# Cpcis_connectors_P4_P5_P6.net
KiCad netlist of a schematic drawn in Altium Designer
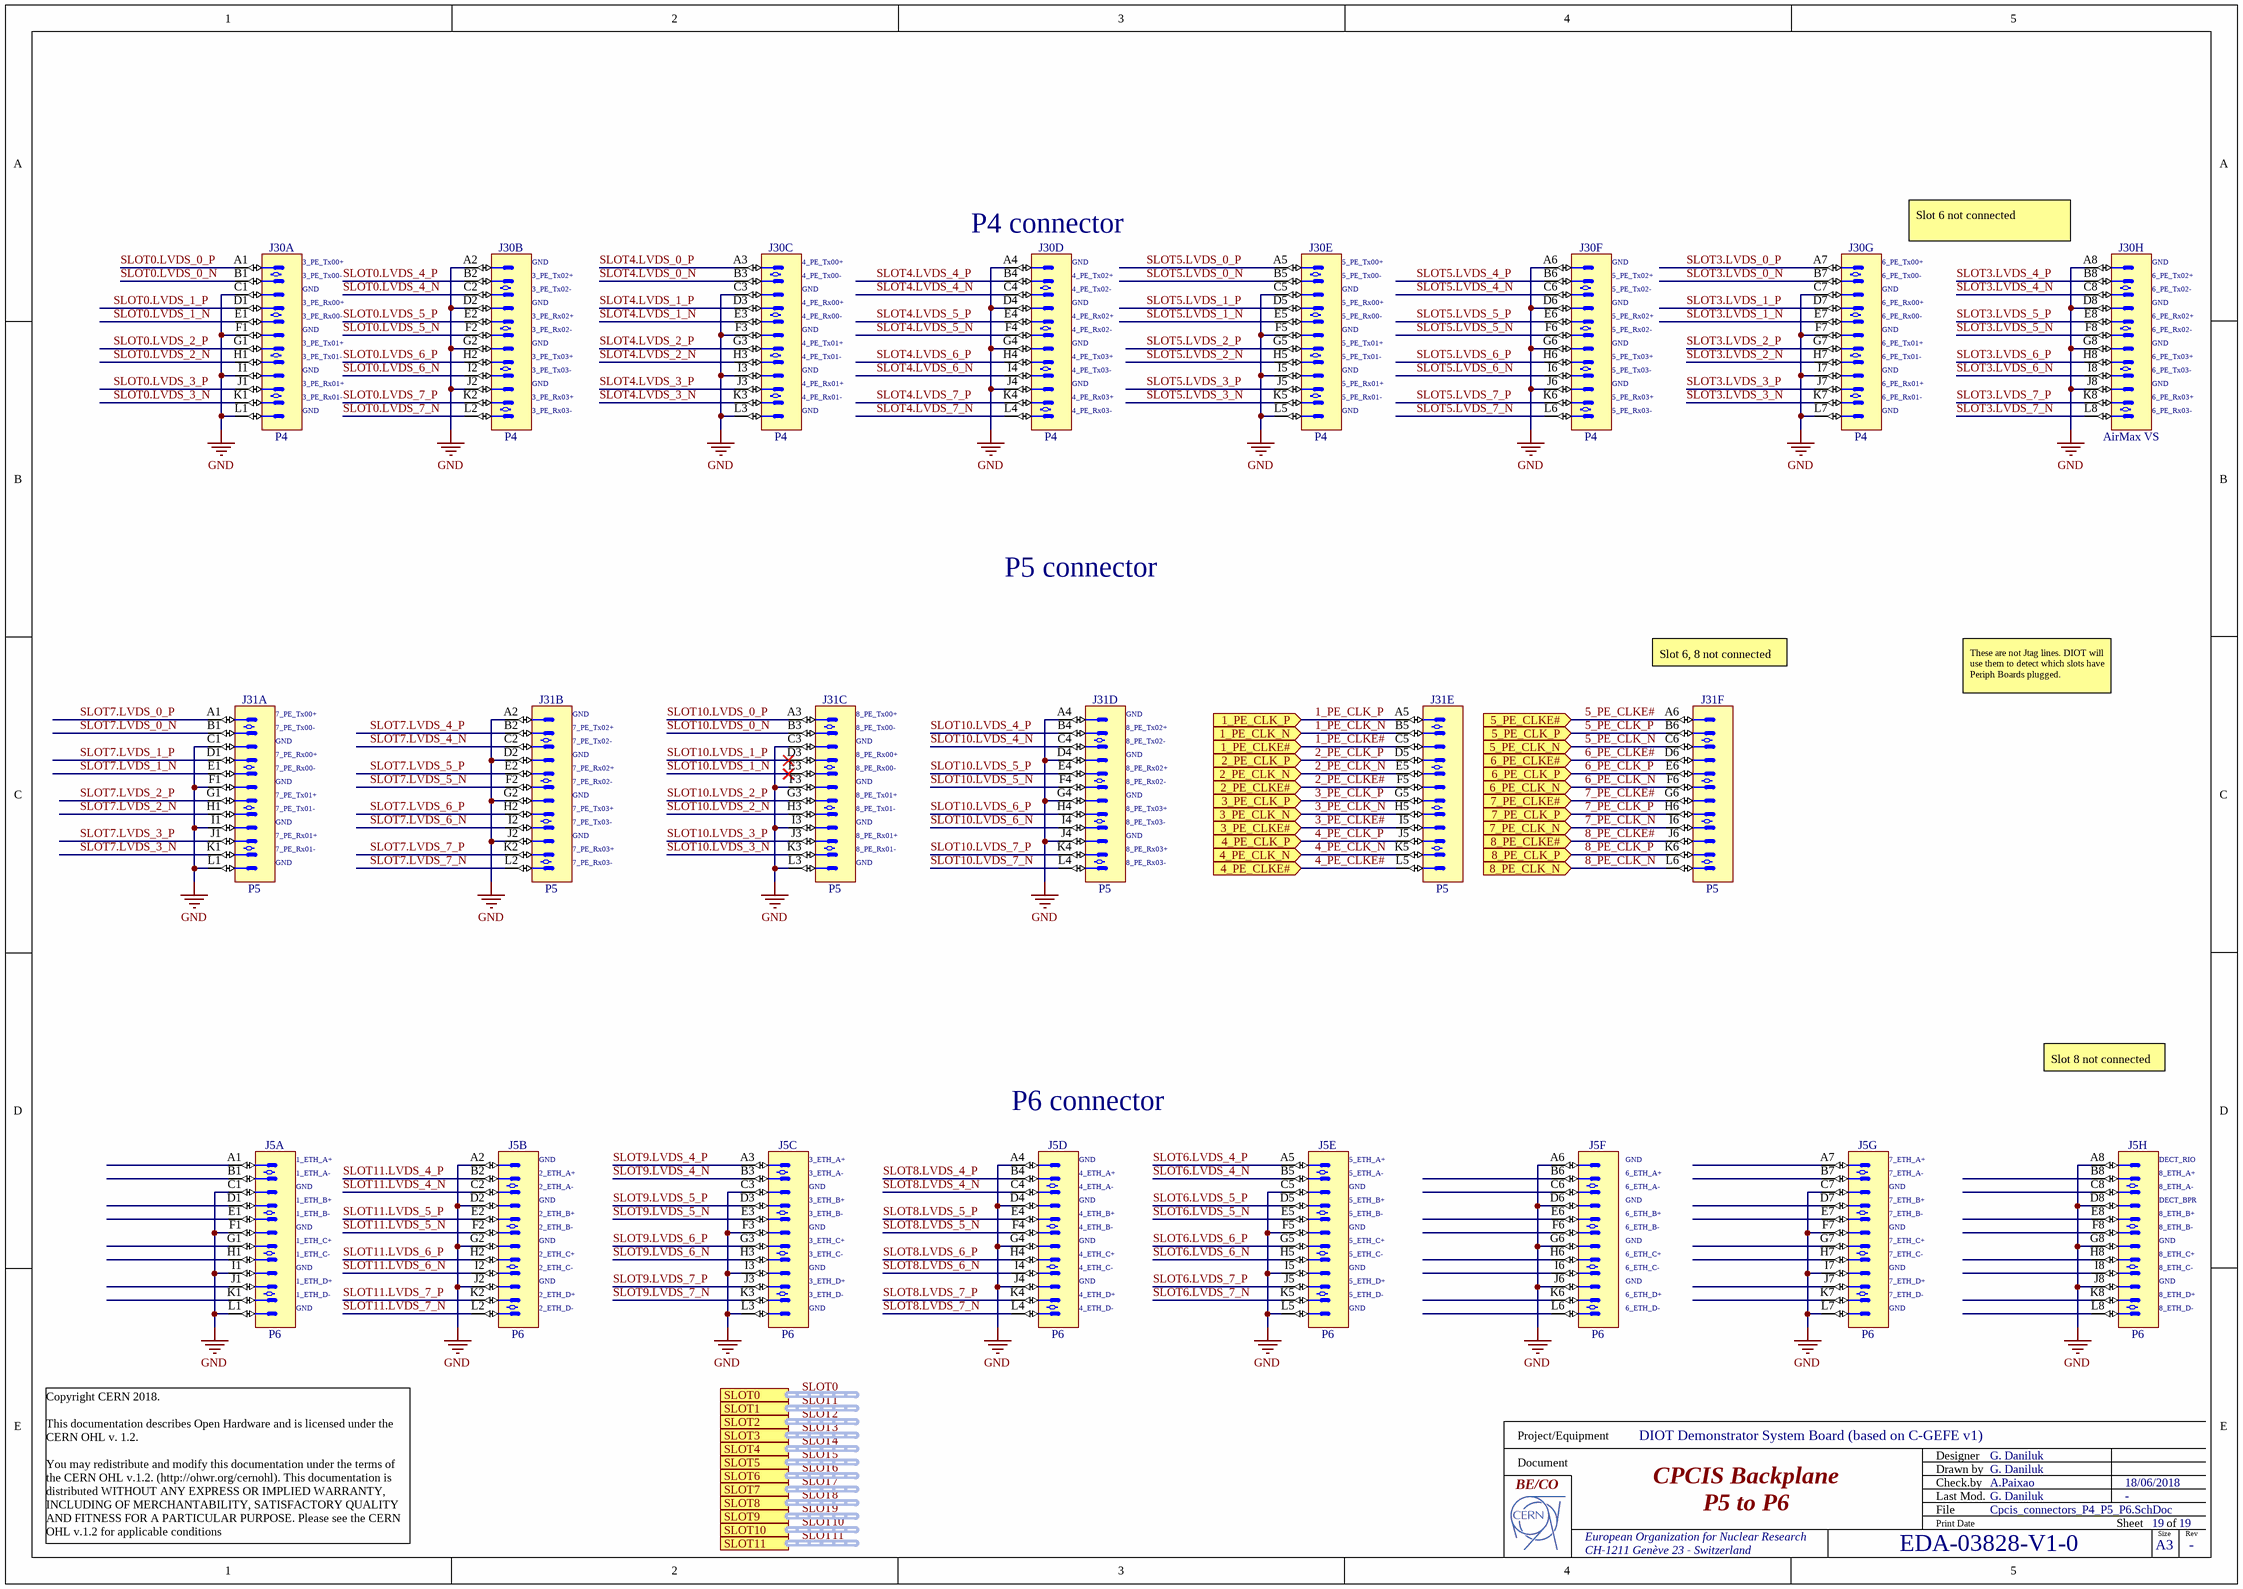
[diagram p0: Cpcis_connectors_P4_P5_P6.SchDoc]

(export (version "E")
  (design (tool "Eeschema 10.0.6"))
  (components
    (comp (ref "J5")
      (value "P6")
      (footprint "AMPHENOL_10052838-101LF")
      (description "96 Contacts Header, 8 Columns, 4 Pairs per Column")
      (fields
        (field (name "PART NUMBER") "AMPHENOL_10052838-101LF")
        (field (name "MANUFACTURER") "AMPHENOL")
        (field (name "AUTHOR") "CERN DEM MR")
      )
      (libsource (lib "Connectors") (part "AMPHENOL_10052838-101LF"))
    )
    (comp (ref "J30")
      (value "P4")
      (footprint "AMPHENOL_10052837-101LF")
      (description "96 Contacts Header, 8 Columns, 4 Pairs per Column")
      (fields
        (field (name "PART NUMBER") "AMPHENOL_10052837-101LF")
        (field (name "MANUFACTURER") "AMPHENOL")
        (field (name "AUTHOR") "CERN DEM MR")
      )
      (libsource (lib "Connectors") (part "AMPHENOL_10052837-101LF"))
    )
    (comp (ref "J31")
      (value "P5")
      (footprint "AMPHENOL_10052824-101LF")
      (description "72 Contacts Header, 6 Columns, 4 Pairs per Column")
      (fields
        (field (name "PART NUMBER") "AMPHENOL_10052824-101LF")
        (field (name "MANUFACTURER") "AMPHENOL")
        (field (name "AUTHOR") "CERN DEM JMW")
      )
      (libsource (lib "Connectors") (part "AMPHENOL_10052824-101LF"))
    )
  )
  (nets
    (net (code "13") (name "/1_PE_CLKE#") (class "Default")
      (node (ref "J31") (pin "C5") (pinfunction "C5_C5") (pintype "bidirectional"))
    )
    (net (code "14") (name "/1_PE_CLK_N") (class "Default")
      (node (ref "J31") (pin "B5") (pinfunction "B5_B5") (pintype "bidirectional"))
    )
    (net (code "15") (name "/1_PE_CLK_P") (class "Default")
      (node (ref "J31") (pin "A5") (pinfunction "A5_A5") (pintype "bidirectional"))
    )
    (net (code "16") (name "/2_PE_CLKE#") (class "Default")
      (node (ref "J31") (pin "F5") (pinfunction "F5_F5") (pintype "bidirectional"))
    )
    (net (code "17") (name "/2_PE_CLK_N") (class "Default")
      (node (ref "J31") (pin "E5") (pinfunction "E5_E5") (pintype "bidirectional"))
    )
    (net (code "18") (name "/2_PE_CLK_P") (class "Default")
      (node (ref "J31") (pin "D5") (pinfunction "D5_D5") (pintype "bidirectional"))
    )
    (net (code "19") (name "/3_PE_CLKE#") (class "Default")
      (node (ref "J31") (pin "I5") (pinfunction "I5_I5") (pintype "bidirectional"))
    )
    (net (code "20") (name "/3_PE_CLK_N") (class "Default")
      (node (ref "J31") (pin "H5") (pinfunction "H5_H5") (pintype "bidirectional"))
    )
    (net (code "21") (name "/3_PE_CLK_P") (class "Default")
      (node (ref "J31") (pin "G5") (pinfunction "G5_G5") (pintype "bidirectional"))
    )
    (net (code "22") (name "/4_PE_CLKE#") (class "Default")
      (node (ref "J31") (pin "L5") (pinfunction "L5_L5") (pintype "bidirectional"))
    )
    (net (code "23") (name "/4_PE_CLK_N") (class "Default")
      (node (ref "J31") (pin "K5") (pinfunction "K5_K5") (pintype "bidirectional"))
    )
    (net (code "24") (name "/4_PE_CLK_P") (class "Default")
      (node (ref "J31") (pin "J5") (pinfunction "J5_J5") (pintype "bidirectional"))
    )
    (net (code "25") (name "/5_PE_CLKE#") (class "Default")
      (node (ref "J31") (pin "A6") (pinfunction "A6_A6") (pintype "bidirectional"))
    )
    (net (code "26") (name "/5_PE_CLK_N") (class "Default")
      (node (ref "J31") (pin "C6") (pinfunction "C6_C6") (pintype "bidirectional"))
    )
    (net (code "27") (name "/5_PE_CLK_P") (class "Default")
      (node (ref "J31") (pin "B6") (pinfunction "B6_B6") (pintype "bidirectional"))
    )
    (net (code "28") (name "/6_PE_CLKE#") (class "Default")
      (node (ref "J31") (pin "D6") (pinfunction "D6_D6") (pintype "bidirectional"))
    )
    (net (code "29") (name "/6_PE_CLK_N") (class "Default")
      (node (ref "J31") (pin "F6") (pinfunction "F6_F6") (pintype "bidirectional"))
    )
    (net (code "30") (name "/6_PE_CLK_P") (class "Default")
      (node (ref "J31") (pin "E6") (pinfunction "E6_E6") (pintype "bidirectional"))
    )
    (net (code "31") (name "/7_PE_CLKE#") (class "Default")
      (node (ref "J31") (pin "G6") (pinfunction "G6_G6") (pintype "bidirectional"))
    )
    (net (code "32") (name "/7_PE_CLK_N") (class "Default")
      (node (ref "J31") (pin "I6") (pinfunction "I6_I6") (pintype "bidirectional"))
    )
    (net (code "33") (name "/7_PE_CLK_P") (class "Default")
      (node (ref "J31") (pin "H6") (pinfunction "H6_H6") (pintype "bidirectional"))
    )
    (net (code "34") (name "/8_PE_CLKE#") (class "Default")
      (node (ref "J31") (pin "J6") (pinfunction "J6_J6") (pintype "bidirectional"))
    )
    (net (code "35") (name "/8_PE_CLK_N") (class "Default")
      (node (ref "J31") (pin "L6") (pinfunction "L6_L6") (pintype "bidirectional"))
    )
    (net (code "36") (name "/8_PE_CLK_P") (class "Default")
      (node (ref "J31") (pin "K6") (pinfunction "K6_K6") (pintype "bidirectional"))
    )
    (net (code "37") (name "/SLOT0.LVDS_0_N") (class "Default")
      (node (ref "J30") (pin "B1") (pinfunction "B1_B1") (pintype "bidirectional"))
    )
    (net (code "38") (name "/SLOT0.LVDS_0_P") (class "Default")
      (node (ref "J30") (pin "A1") (pinfunction "A1_A1") (pintype "bidirectional"))
    )
    (net (code "39") (name "/SLOT0.LVDS_1_N") (class "Default")
      (node (ref "J30") (pin "E1") (pinfunction "E1_E1") (pintype "bidirectional"))
    )
    (net (code "40") (name "/SLOT0.LVDS_1_P") (class "Default")
      (node (ref "J30") (pin "D1") (pinfunction "D1_D1") (pintype "bidirectional"))
    )
    (net (code "41") (name "/SLOT0.LVDS_2_N") (class "Default")
      (node (ref "J30") (pin "H1") (pinfunction "H1_H1") (pintype "bidirectional"))
    )
    (net (code "42") (name "/SLOT0.LVDS_2_P") (class "Default")
      (node (ref "J30") (pin "G1") (pinfunction "G1_G1") (pintype "bidirectional"))
    )
    (net (code "43") (name "/SLOT0.LVDS_3_N") (class "Default")
      (node (ref "J30") (pin "K1") (pinfunction "K1_K1") (pintype "bidirectional"))
    )
    (net (code "44") (name "/SLOT0.LVDS_3_P") (class "Default")
      (node (ref "J30") (pin "J1") (pinfunction "J1_J1") (pintype "bidirectional"))
    )
    (net (code "45") (name "/SLOT0.LVDS_4_N") (class "Default")
      (node (ref "J30") (pin "C2") (pinfunction "C2_C2") (pintype "bidirectional"))
    )
    (net (code "46") (name "/SLOT0.LVDS_4_P") (class "Default")
      (node (ref "J30") (pin "B2") (pinfunction "B2_B2") (pintype "bidirectional"))
    )
    (net (code "47") (name "/SLOT0.LVDS_5_N") (class "Default")
      (node (ref "J30") (pin "F2") (pinfunction "F2_F2") (pintype "bidirectional"))
    )
    (net (code "48") (name "/SLOT0.LVDS_5_P") (class "Default")
      (node (ref "J30") (pin "E2") (pinfunction "E2_E2") (pintype "bidirectional"))
    )
    (net (code "49") (name "/SLOT0.LVDS_6_N") (class "Default")
      (node (ref "J30") (pin "I2") (pinfunction "I2_I2") (pintype "bidirectional"))
    )
    (net (code "50") (name "/SLOT0.LVDS_6_P") (class "Default")
      (node (ref "J30") (pin "H2") (pinfunction "H2_H2") (pintype "bidirectional"))
    )
    (net (code "51") (name "/SLOT0.LVDS_7_N") (class "Default")
      (node (ref "J30") (pin "L2") (pinfunction "L2_L2") (pintype "bidirectional"))
    )
    (net (code "52") (name "/SLOT0.LVDS_7_P") (class "Default")
      (node (ref "J30") (pin "K2") (pinfunction "K2_K2") (pintype "bidirectional"))
    )
    (net (code "53") (name "/SLOT3.LVDS_0_N") (class "Default")
      (node (ref "J30") (pin "B7") (pinfunction "B7_B7") (pintype "bidirectional"))
    )
    (net (code "54") (name "/SLOT3.LVDS_0_P") (class "Default")
      (node (ref "J30") (pin "A7") (pinfunction "A7_A7") (pintype "bidirectional"))
    )
    (net (code "55") (name "/SLOT3.LVDS_1_N") (class "Default")
      (node (ref "J30") (pin "E7") (pinfunction "E7_E7") (pintype "bidirectional"))
    )
    (net (code "56") (name "/SLOT3.LVDS_1_P") (class "Default")
      (node (ref "J30") (pin "D7") (pinfunction "D7_D7") (pintype "bidirectional"))
    )
    (net (code "57") (name "/SLOT3.LVDS_2_N") (class "Default")
      (node (ref "J30") (pin "H7") (pinfunction "H7_H7") (pintype "bidirectional"))
    )
    (net (code "58") (name "/SLOT3.LVDS_2_P") (class "Default")
      (node (ref "J30") (pin "G7") (pinfunction "G7_G7") (pintype "bidirectional"))
    )
    (net (code "59") (name "/SLOT3.LVDS_3_N") (class "Default")
      (node (ref "J30") (pin "K7") (pinfunction "K7_K7") (pintype "bidirectional"))
    )
    (net (code "60") (name "/SLOT3.LVDS_3_P") (class "Default")
      (node (ref "J30") (pin "J7") (pinfunction "J7_J7") (pintype "bidirectional"))
    )
    (net (code "61") (name "/SLOT3.LVDS_4_N") (class "Default")
      (node (ref "J30") (pin "C8") (pinfunction "C8_C8") (pintype "bidirectional"))
    )
    (net (code "62") (name "/SLOT3.LVDS_4_P") (class "Default")
      (node (ref "J30") (pin "B8") (pinfunction "B8_B8") (pintype "bidirectional"))
    )
    (net (code "63") (name "/SLOT3.LVDS_5_N") (class "Default")
      (node (ref "J30") (pin "F8") (pinfunction "F8_F8") (pintype "bidirectional"))
    )
    (net (code "64") (name "/SLOT3.LVDS_5_P") (class "Default")
      (node (ref "J30") (pin "E8") (pinfunction "E8_E8") (pintype "bidirectional"))
    )
    (net (code "65") (name "/SLOT3.LVDS_6_N") (class "Default")
      (node (ref "J30") (pin "I8") (pinfunction "I8_I8") (pintype "bidirectional"))
    )
    (net (code "66") (name "/SLOT3.LVDS_6_P") (class "Default")
      (node (ref "J30") (pin "H8") (pinfunction "H8_H8") (pintype "bidirectional"))
    )
    (net (code "67") (name "/SLOT3.LVDS_7_N") (class "Default")
      (node (ref "J30") (pin "L8") (pinfunction "L8_L8") (pintype "bidirectional"))
    )
    (net (code "68") (name "/SLOT3.LVDS_7_P") (class "Default")
      (node (ref "J30") (pin "K8") (pinfunction "K8_K8") (pintype "bidirectional"))
    )
    (net (code "69") (name "/SLOT4.LVDS_0_N") (class "Default")
      (node (ref "J30") (pin "B3") (pinfunction "B3_B3") (pintype "bidirectional"))
    )
    (net (code "70") (name "/SLOT4.LVDS_0_P") (class "Default")
      (node (ref "J30") (pin "A3") (pinfunction "A3_A3") (pintype "bidirectional"))
    )
    (net (code "71") (name "/SLOT4.LVDS_1_N") (class "Default")
      (node (ref "J30") (pin "E3") (pinfunction "E3_E3") (pintype "bidirectional"))
    )
    (net (code "72") (name "/SLOT4.LVDS_1_P") (class "Default")
      (node (ref "J30") (pin "D3") (pinfunction "D3_D3") (pintype "bidirectional"))
    )
    (net (code "73") (name "/SLOT4.LVDS_2_N") (class "Default")
      (node (ref "J30") (pin "H3") (pinfunction "H3_H3") (pintype "bidirectional"))
    )
    (net (code "74") (name "/SLOT4.LVDS_2_P") (class "Default")
      (node (ref "J30") (pin "G3") (pinfunction "G3_G3") (pintype "bidirectional"))
    )
    (net (code "75") (name "/SLOT4.LVDS_3_N") (class "Default")
      (node (ref "J30") (pin "K3") (pinfunction "K3_K3") (pintype "bidirectional"))
    )
    (net (code "76") (name "/SLOT4.LVDS_3_P") (class "Default")
      (node (ref "J30") (pin "J3") (pinfunction "J3_J3") (pintype "bidirectional"))
    )
    (net (code "77") (name "/SLOT4.LVDS_4_N") (class "Default")
      (node (ref "J30") (pin "C4") (pinfunction "C4_C4") (pintype "bidirectional"))
    )
    (net (code "78") (name "/SLOT4.LVDS_4_P") (class "Default")
      (node (ref "J30") (pin "B4") (pinfunction "B4_B4") (pintype "bidirectional"))
    )
    (net (code "79") (name "/SLOT4.LVDS_5_N") (class "Default")
      (node (ref "J30") (pin "F4") (pinfunction "F4_F4") (pintype "bidirectional"))
    )
    (net (code "80") (name "/SLOT4.LVDS_5_P") (class "Default")
      (node (ref "J30") (pin "E4") (pinfunction "E4_E4") (pintype "bidirectional"))
    )
    (net (code "81") (name "/SLOT4.LVDS_6_N") (class "Default")
      (node (ref "J30") (pin "I4") (pinfunction "I4_I4") (pintype "bidirectional"))
    )
    (net (code "82") (name "/SLOT4.LVDS_6_P") (class "Default")
      (node (ref "J30") (pin "H4") (pinfunction "H4_H4") (pintype "bidirectional"))
    )
    (net (code "83") (name "/SLOT4.LVDS_7_N") (class "Default")
      (node (ref "J30") (pin "L4") (pinfunction "L4_L4") (pintype "bidirectional"))
    )
    (net (code "84") (name "/SLOT4.LVDS_7_P") (class "Default")
      (node (ref "J30") (pin "K4") (pinfunction "K4_K4") (pintype "bidirectional"))
    )
    (net (code "85") (name "/SLOT5.LVDS_0_N") (class "Default")
      (node (ref "J30") (pin "B5") (pinfunction "B5_B5") (pintype "bidirectional"))
    )
    (net (code "86") (name "/SLOT5.LVDS_0_P") (class "Default")
      (node (ref "J30") (pin "A5") (pinfunction "A5_A5") (pintype "bidirectional"))
    )
    (net (code "87") (name "/SLOT5.LVDS_1_N") (class "Default")
      (node (ref "J30") (pin "E5") (pinfunction "E5_E5") (pintype "bidirectional"))
    )
    (net (code "88") (name "/SLOT5.LVDS_1_P") (class "Default")
      (node (ref "J30") (pin "D5") (pinfunction "D5_D5") (pintype "bidirectional"))
    )
    (net (code "89") (name "/SLOT5.LVDS_2_N") (class "Default")
      (node (ref "J30") (pin "H5") (pinfunction "H5_H5") (pintype "bidirectional"))
    )
    (net (code "90") (name "/SLOT5.LVDS_2_P") (class "Default")
      (node (ref "J30") (pin "G5") (pinfunction "G5_G5") (pintype "bidirectional"))
    )
    (net (code "91") (name "/SLOT5.LVDS_3_N") (class "Default")
      (node (ref "J30") (pin "K5") (pinfunction "K5_K5") (pintype "bidirectional"))
    )
    (net (code "92") (name "/SLOT5.LVDS_3_P") (class "Default")
      (node (ref "J30") (pin "J5") (pinfunction "J5_J5") (pintype "bidirectional"))
    )
    (net (code "93") (name "/SLOT5.LVDS_4_N") (class "Default")
      (node (ref "J30") (pin "C6") (pinfunction "C6_C6") (pintype "bidirectional"))
    )
    (net (code "94") (name "/SLOT5.LVDS_4_P") (class "Default")
      (node (ref "J30") (pin "B6") (pinfunction "B6_B6") (pintype "bidirectional"))
    )
    (net (code "95") (name "/SLOT5.LVDS_5_N") (class "Default")
      (node (ref "J30") (pin "F6") (pinfunction "F6_F6") (pintype "bidirectional"))
    )
    (net (code "96") (name "/SLOT5.LVDS_5_P") (class "Default")
      (node (ref "J30") (pin "E6") (pinfunction "E6_E6") (pintype "bidirectional"))
    )
    (net (code "97") (name "/SLOT5.LVDS_6_N") (class "Default")
      (node (ref "J30") (pin "I6") (pinfunction "I6_I6") (pintype "bidirectional"))
    )
    (net (code "98") (name "/SLOT5.LVDS_6_P") (class "Default")
      (node (ref "J30") (pin "H6") (pinfunction "H6_H6") (pintype "bidirectional"))
    )
    (net (code "99") (name "/SLOT5.LVDS_7_N") (class "Default")
      (node (ref "J30") (pin "L6") (pinfunction "L6_L6") (pintype "bidirectional"))
    )
    (net (code "100") (name "/SLOT5.LVDS_7_P") (class "Default")
      (node (ref "J30") (pin "K6") (pinfunction "K6_K6") (pintype "bidirectional"))
    )
    (net (code "101") (name "/SLOT6.LVDS_4_N") (class "Default")
      (node (ref "J5") (pin "B5") (pinfunction "B5_B5") (pintype "bidirectional"))
    )
    (net (code "102") (name "/SLOT6.LVDS_4_P") (class "Default")
      (node (ref "J5") (pin "A5") (pinfunction "A5_A5") (pintype "bidirectional"))
    )
    (net (code "103") (name "/SLOT6.LVDS_5_N") (class "Default")
      (node (ref "J5") (pin "E5") (pinfunction "E5_E5") (pintype "bidirectional"))
    )
    (net (code "104") (name "/SLOT6.LVDS_5_P") (class "Default")
      (node (ref "J5") (pin "D5") (pinfunction "D5_D5") (pintype "bidirectional"))
    )
    (net (code "105") (name "/SLOT6.LVDS_6_N") (class "Default")
      (node (ref "J5") (pin "H5") (pinfunction "H5_H5") (pintype "bidirectional"))
    )
    (net (code "106") (name "/SLOT6.LVDS_6_P") (class "Default")
      (node (ref "J5") (pin "G5") (pinfunction "G5_G5") (pintype "bidirectional"))
    )
    (net (code "107") (name "/SLOT6.LVDS_7_N") (class "Default")
      (node (ref "J5") (pin "K5") (pinfunction "K5_K5") (pintype "bidirectional"))
    )
    (net (code "108") (name "/SLOT6.LVDS_7_P") (class "Default")
      (node (ref "J5") (pin "J5") (pinfunction "J5_J5") (pintype "bidirectional"))
    )
    (net (code "109") (name "/SLOT7.LVDS_0_N") (class "Default")
      (node (ref "J31") (pin "B1") (pinfunction "B1_B1") (pintype "bidirectional"))
    )
    (net (code "110") (name "/SLOT7.LVDS_0_P") (class "Default")
      (node (ref "J31") (pin "A1") (pinfunction "A1_A1") (pintype "bidirectional"))
    )
    (net (code "111") (name "/SLOT7.LVDS_1_N") (class "Default")
      (node (ref "J31") (pin "E1") (pinfunction "E1_E1") (pintype "bidirectional"))
    )
    (net (code "112") (name "/SLOT7.LVDS_1_P") (class "Default")
      (node (ref "J31") (pin "D1") (pinfunction "D1_D1") (pintype "bidirectional"))
    )
    (net (code "113") (name "/SLOT7.LVDS_2_N") (class "Default")
      (node (ref "J31") (pin "H1") (pinfunction "H1_H1") (pintype "bidirectional"))
    )
    (net (code "114") (name "/SLOT7.LVDS_2_P") (class "Default")
      (node (ref "J31") (pin "G1") (pinfunction "G1_G1") (pintype "bidirectional"))
    )
    (net (code "115") (name "/SLOT7.LVDS_3_N") (class "Default")
      (node (ref "J31") (pin "K1") (pinfunction "K1_K1") (pintype "bidirectional"))
    )
    (net (code "116") (name "/SLOT7.LVDS_3_P") (class "Default")
      (node (ref "J31") (pin "J1") (pinfunction "J1_J1") (pintype "bidirectional"))
    )
    (net (code "117") (name "/SLOT7.LVDS_4_N") (class "Default")
      (node (ref "J31") (pin "C2") (pinfunction "C2_C2") (pintype "bidirectional"))
    )
    (net (code "118") (name "/SLOT7.LVDS_4_P") (class "Default")
      (node (ref "J31") (pin "B2") (pinfunction "B2_B2") (pintype "bidirectional"))
    )
    (net (code "119") (name "/SLOT7.LVDS_5_N") (class "Default")
      (node (ref "J31") (pin "F2") (pinfunction "F2_F2") (pintype "bidirectional"))
    )
    (net (code "120") (name "/SLOT7.LVDS_5_P") (class "Default")
      (node (ref "J31") (pin "E2") (pinfunction "E2_E2") (pintype "bidirectional"))
    )
    (net (code "121") (name "/SLOT7.LVDS_6_N") (class "Default")
      (node (ref "J31") (pin "I2") (pinfunction "I2_I2") (pintype "bidirectional"))
    )
    (net (code "122") (name "/SLOT7.LVDS_6_P") (class "Default")
      (node (ref "J31") (pin "H2") (pinfunction "H2_H2") (pintype "bidirectional"))
    )
    (net (code "123") (name "/SLOT7.LVDS_7_N") (class "Default")
      (node (ref "J31") (pin "L2") (pinfunction "L2_L2") (pintype "bidirectional"))
    )
    (net (code "124") (name "/SLOT7.LVDS_7_P") (class "Default")
      (node (ref "J31") (pin "K2") (pinfunction "K2_K2") (pintype "bidirectional"))
    )
    (net (code "125") (name "/SLOT8.LVDS_4_N") (class "Default")
      (node (ref "J5") (pin "C4") (pinfunction "C4_C4") (pintype "bidirectional"))
    )
    (net (code "126") (name "/SLOT8.LVDS_4_P") (class "Default")
      (node (ref "J5") (pin "B4") (pinfunction "B4_B4") (pintype "bidirectional"))
    )
    (net (code "127") (name "/SLOT8.LVDS_5_N") (class "Default")
      (node (ref "J5") (pin "F4") (pinfunction "F4_F4") (pintype "bidirectional"))
    )
    (net (code "128") (name "/SLOT8.LVDS_5_P") (class "Default")
      (node (ref "J5") (pin "E4") (pinfunction "E4_E4") (pintype "bidirectional"))
    )
    (net (code "129") (name "/SLOT8.LVDS_6_N") (class "Default")
      (node (ref "J5") (pin "I4") (pinfunction "I4_I4") (pintype "bidirectional"))
    )
    (net (code "130") (name "/SLOT8.LVDS_6_P") (class "Default")
      (node (ref "J5") (pin "H4") (pinfunction "H4_H4") (pintype "bidirectional"))
    )
    (net (code "131") (name "/SLOT8.LVDS_7_N") (class "Default")
      (node (ref "J5") (pin "L4") (pinfunction "L4_L4") (pintype "bidirectional"))
    )
    (net (code "132") (name "/SLOT8.LVDS_7_P") (class "Default")
      (node (ref "J5") (pin "K4") (pinfunction "K4_K4") (pintype "bidirectional"))
    )
    (net (code "133") (name "/SLOT9.LVDS_4_N") (class "Default")
      (node (ref "J5") (pin "B3") (pinfunction "B3_B3") (pintype "bidirectional"))
    )
    (net (code "134") (name "/SLOT9.LVDS_4_P") (class "Default")
      (node (ref "J5") (pin "A3") (pinfunction "A3_A3") (pintype "bidirectional"))
    )
    (net (code "135") (name "/SLOT9.LVDS_5_N") (class "Default")
      (node (ref "J5") (pin "E3") (pinfunction "E3_E3") (pintype "bidirectional"))
    )
    (net (code "136") (name "/SLOT9.LVDS_5_P") (class "Default")
      (node (ref "J5") (pin "D3") (pinfunction "D3_D3") (pintype "bidirectional"))
    )
    (net (code "137") (name "/SLOT9.LVDS_6_N") (class "Default")
      (node (ref "J5") (pin "H3") (pinfunction "H3_H3") (pintype "bidirectional"))
    )
    (net (code "138") (name "/SLOT9.LVDS_6_P") (class "Default")
      (node (ref "J5") (pin "G3") (pinfunction "G3_G3") (pintype "bidirectional"))
    )
    (net (code "139") (name "/SLOT9.LVDS_7_N") (class "Default")
      (node (ref "J5") (pin "K3") (pinfunction "K3_K3") (pintype "bidirectional"))
    )
    (net (code "140") (name "/SLOT9.LVDS_7_P") (class "Default")
      (node (ref "J5") (pin "J3") (pinfunction "J3_J3") (pintype "bidirectional"))
    )
    (net (code "141") (name "/SLOT10.LVDS_0_N") (class "Default")
      (node (ref "J31") (pin "B3") (pinfunction "B3_B3") (pintype "bidirectional"))
    )
    (net (code "142") (name "/SLOT10.LVDS_0_P") (class "Default")
      (node (ref "J31") (pin "A3") (pinfunction "A3_A3") (pintype "bidirectional"))
    )
    (net (code "143") (name "/SLOT10.LVDS_1_N") (class "Default")
      (node (ref "J31") (pin "E3") (pinfunction "E3_E3") (pintype "bidirectional+no_connect"))
    )
    (net (code "144") (name "/SLOT10.LVDS_1_P") (class "Default")
      (node (ref "J31") (pin "D3") (pinfunction "D3_D3") (pintype "bidirectional+no_connect"))
    )
    (net (code "145") (name "/SLOT10.LVDS_2_N") (class "Default")
      (node (ref "J31") (pin "H3") (pinfunction "H3_H3") (pintype "bidirectional"))
    )
    (net (code "146") (name "/SLOT10.LVDS_2_P") (class "Default")
      (node (ref "J31") (pin "G3") (pinfunction "G3_G3") (pintype "bidirectional"))
    )
    (net (code "147") (name "/SLOT10.LVDS_3_N") (class "Default")
      (node (ref "J31") (pin "K3") (pinfunction "K3_K3") (pintype "bidirectional"))
    )
    (net (code "148") (name "/SLOT10.LVDS_3_P") (class "Default")
      (node (ref "J31") (pin "J3") (pinfunction "J3_J3") (pintype "bidirectional"))
    )
    (net (code "149") (name "/SLOT10.LVDS_4_N") (class "Default")
      (node (ref "J31") (pin "C4") (pinfunction "C4_C4") (pintype "bidirectional"))
    )
    (net (code "150") (name "/SLOT10.LVDS_4_P") (class "Default")
      (node (ref "J31") (pin "B4") (pinfunction "B4_B4") (pintype "bidirectional"))
    )
    (net (code "151") (name "/SLOT10.LVDS_5_N") (class "Default")
      (node (ref "J31") (pin "F4") (pinfunction "F4_F4") (pintype "bidirectional"))
    )
    (net (code "152") (name "/SLOT10.LVDS_5_P") (class "Default")
      (node (ref "J31") (pin "E4") (pinfunction "E4_E4") (pintype "bidirectional"))
    )
    (net (code "153") (name "/SLOT10.LVDS_6_N") (class "Default")
      (node (ref "J31") (pin "I4") (pinfunction "I4_I4") (pintype "bidirectional"))
    )
    (net (code "154") (name "/SLOT10.LVDS_6_P") (class "Default")
      (node (ref "J31") (pin "H4") (pinfunction "H4_H4") (pintype "bidirectional"))
    )
    (net (code "155") (name "/SLOT10.LVDS_7_N") (class "Default")
      (node (ref "J31") (pin "L4") (pinfunction "L4_L4") (pintype "bidirectional"))
    )
    (net (code "156") (name "/SLOT10.LVDS_7_P") (class "Default")
      (node (ref "J31") (pin "K4") (pinfunction "K4_K4") (pintype "bidirectional"))
    )
    (net (code "157") (name "/SLOT11.LVDS_4_N") (class "Default")
      (node (ref "J5") (pin "C2") (pinfunction "C2_C2") (pintype "bidirectional"))
    )
    (net (code "158") (name "/SLOT11.LVDS_4_P") (class "Default")
      (node (ref "J5") (pin "B2") (pinfunction "B2_B2") (pintype "bidirectional"))
    )
    (net (code "159") (name "/SLOT11.LVDS_5_N") (class "Default")
      (node (ref "J5") (pin "F2") (pinfunction "F2_F2") (pintype "bidirectional"))
    )
    (net (code "160") (name "/SLOT11.LVDS_5_P") (class "Default")
      (node (ref "J5") (pin "E2") (pinfunction "E2_E2") (pintype "bidirectional"))
    )
    (net (code "161") (name "/SLOT11.LVDS_6_N") (class "Default")
      (node (ref "J5") (pin "I2") (pinfunction "I2_I2") (pintype "bidirectional"))
    )
    (net (code "162") (name "/SLOT11.LVDS_6_P") (class "Default")
      (node (ref "J5") (pin "H2") (pinfunction "H2_H2") (pintype "bidirectional"))
    )
    (net (code "163") (name "/SLOT11.LVDS_7_N") (class "Default")
      (node (ref "J5") (pin "L2") (pinfunction "L2_L2") (pintype "bidirectional"))
    )
    (net (code "164") (name "/SLOT11.LVDS_7_P") (class "Default")
      (node (ref "J5") (pin "K2") (pinfunction "K2_K2") (pintype "bidirectional"))
    )
    (net (code "177") (name "GND") (class "Default")
      (node (ref "J30") (pin "A2") (pinfunction "A2_A2") (pintype "bidirectional"))
      (node (ref "J30") (pin "A4") (pinfunction "A4_A4") (pintype "bidirectional"))
      (node (ref "J30") (pin "A6") (pinfunction "A6_A6") (pintype "bidirectional"))
      (node (ref "J30") (pin "A8") (pinfunction "A8_A8") (pintype "bidirectional"))
      (node (ref "J30") (pin "C1") (pinfunction "C1_C1") (pintype "bidirectional"))
      (node (ref "J30") (pin "C3") (pinfunction "C3_C3") (pintype "bidirectional"))
      (node (ref "J30") (pin "C5") (pinfunction "C5_C5") (pintype "bidirectional"))
      (node (ref "J30") (pin "C7") (pinfunction "C7_C7") (pintype "bidirectional"))
      (node (ref "J30") (pin "D2") (pinfunction "D2_D2") (pintype "bidirectional"))
      (node (ref "J30") (pin "D4") (pinfunction "D4_D4") (pintype "bidirectional"))
      (node (ref "J30") (pin "D6") (pinfunction "D6_D6") (pintype "bidirectional"))
      (node (ref "J30") (pin "D8") (pinfunction "D8_D8") (pintype "bidirectional"))
      (node (ref "J30") (pin "F1") (pinfunction "F1_F1") (pintype "bidirectional"))
      (node (ref "J30") (pin "F3") (pinfunction "F3_F3") (pintype "bidirectional"))
      (node (ref "J30") (pin "F5") (pinfunction "F5_F5") (pintype "bidirectional"))
      (node (ref "J30") (pin "F7") (pinfunction "F7_F7") (pintype "bidirectional"))
      (node (ref "J30") (pin "G2") (pinfunction "G2_G2") (pintype "bidirectional"))
      (node (ref "J30") (pin "G4") (pinfunction "G4_G4") (pintype "bidirectional"))
      (node (ref "J30") (pin "G6") (pinfunction "G6_G6") (pintype "bidirectional"))
      (node (ref "J30") (pin "G8") (pinfunction "G8_G8") (pintype "bidirectional"))
      (node (ref "J30") (pin "I1") (pinfunction "I1_I1") (pintype "bidirectional"))
      (node (ref "J30") (pin "I3") (pinfunction "I3_I3") (pintype "bidirectional"))
      (node (ref "J30") (pin "I5") (pinfunction "I5_I5") (pintype "bidirectional"))
      (node (ref "J30") (pin "I7") (pinfunction "I7_I7") (pintype "bidirectional"))
      (node (ref "J30") (pin "J2") (pinfunction "J2_J2") (pintype "bidirectional"))
      (node (ref "J30") (pin "J4") (pinfunction "J4_J4") (pintype "bidirectional"))
      (node (ref "J30") (pin "J6") (pinfunction "J6_J6") (pintype "bidirectional"))
      (node (ref "J30") (pin "J8") (pinfunction "J8_J8") (pintype "bidirectional"))
      (node (ref "J30") (pin "L1") (pinfunction "L1_L1") (pintype "bidirectional"))
      (node (ref "J30") (pin "L3") (pinfunction "L3_L3") (pintype "bidirectional"))
      (node (ref "J30") (pin "L5") (pinfunction "L5_L5") (pintype "bidirectional"))
      (node (ref "J30") (pin "L7") (pinfunction "L7_L7") (pintype "bidirectional"))
      (node (ref "J31") (pin "A2") (pinfunction "A2_A2") (pintype "bidirectional"))
      (node (ref "J31") (pin "A4") (pinfunction "A4_A4") (pintype "bidirectional"))
      (node (ref "J31") (pin "C1") (pinfunction "C1_C1") (pintype "bidirectional"))
      (node (ref "J31") (pin "C3") (pinfunction "C3_C3") (pintype "bidirectional"))
      (node (ref "J31") (pin "D2") (pinfunction "D2_D2") (pintype "bidirectional"))
      (node (ref "J31") (pin "D4") (pinfunction "D4_D4") (pintype "bidirectional"))
      (node (ref "J31") (pin "F1") (pinfunction "F1_F1") (pintype "bidirectional"))
      (node (ref "J31") (pin "F3") (pinfunction "F3_F3") (pintype "bidirectional"))
      (node (ref "J31") (pin "G2") (pinfunction "G2_G2") (pintype "bidirectional"))
      (node (ref "J31") (pin "G4") (pinfunction "G4_G4") (pintype "bidirectional"))
      (node (ref "J31") (pin "I1") (pinfunction "I1_I1") (pintype "bidirectional"))
      (node (ref "J31") (pin "I3") (pinfunction "I3_I3") (pintype "bidirectional"))
      (node (ref "J31") (pin "J2") (pinfunction "J2_J2") (pintype "bidirectional"))
      (node (ref "J31") (pin "J4") (pinfunction "J4_J4") (pintype "bidirectional"))
      (node (ref "J31") (pin "L1") (pinfunction "L1_L1") (pintype "bidirectional"))
      (node (ref "J31") (pin "L3") (pinfunction "L3_L3") (pintype "bidirectional"))
      (node (ref "J5") (pin "A2") (pinfunction "A2_A2") (pintype "bidirectional"))
      (node (ref "J5") (pin "A4") (pinfunction "A4_A4") (pintype "bidirectional"))
      (node (ref "J5") (pin "A6") (pinfunction "A6_A6") (pintype "bidirectional"))
      (node (ref "J5") (pin "A8") (pinfunction "A8_A8") (pintype "bidirectional"))
      (node (ref "J5") (pin "C1") (pinfunction "C1_C1") (pintype "bidirectional"))
      (node (ref "J5") (pin "C3") (pinfunction "C3_C3") (pintype "bidirectional"))
      (node (ref "J5") (pin "C5") (pinfunction "C5_C5") (pintype "bidirectional"))
      (node (ref "J5") (pin "C7") (pinfunction "C7_C7") (pintype "bidirectional"))
      (node (ref "J5") (pin "D2") (pinfunction "D2_D2") (pintype "bidirectional"))
      (node (ref "J5") (pin "D4") (pinfunction "D4_D4") (pintype "bidirectional"))
      (node (ref "J5") (pin "D6") (pinfunction "D6_D6") (pintype "bidirectional"))
      (node (ref "J5") (pin "D8") (pinfunction "D8_D8") (pintype "bidirectional"))
      (node (ref "J5") (pin "F1") (pinfunction "F1_F1") (pintype "bidirectional"))
      (node (ref "J5") (pin "F3") (pinfunction "F3_F3") (pintype "bidirectional"))
      (node (ref "J5") (pin "F5") (pinfunction "F5_F5") (pintype "bidirectional"))
      (node (ref "J5") (pin "F7") (pinfunction "F7_F7") (pintype "bidirectional"))
      (node (ref "J5") (pin "G2") (pinfunction "G2_G2") (pintype "bidirectional"))
      (node (ref "J5") (pin "G4") (pinfunction "G4_G4") (pintype "bidirectional"))
      (node (ref "J5") (pin "G6") (pinfunction "G6_G6") (pintype "bidirectional"))
      (node (ref "J5") (pin "G8") (pinfunction "G8_G8") (pintype "bidirectional"))
      (node (ref "J5") (pin "I1") (pinfunction "I1_I1") (pintype "bidirectional"))
      (node (ref "J5") (pin "I3") (pinfunction "I3_I3") (pintype "bidirectional"))
      (node (ref "J5") (pin "I5") (pinfunction "I5_I5") (pintype "bidirectional"))
      (node (ref "J5") (pin "I7") (pinfunction "I7_I7") (pintype "bidirectional"))
      (node (ref "J5") (pin "J2") (pinfunction "J2_J2") (pintype "bidirectional"))
      (node (ref "J5") (pin "J4") (pinfunction "J4_J4") (pintype "bidirectional"))
      (node (ref "J5") (pin "J6") (pinfunction "J6_J6") (pintype "bidirectional"))
      (node (ref "J5") (pin "J8") (pinfunction "J8_J8") (pintype "bidirectional"))
      (node (ref "J5") (pin "L1") (pinfunction "L1_L1") (pintype "bidirectional"))
      (node (ref "J5") (pin "L3") (pinfunction "L3_L3") (pintype "bidirectional"))
      (node (ref "J5") (pin "L5") (pinfunction "L5_L5") (pintype "bidirectional"))
      (node (ref "J5") (pin "L7") (pinfunction "L7_L7") (pintype "bidirectional"))
    )
    (net (code "178") (name "unconnected-(J5-PadA1)") (class "Default")
      (node (ref "J5") (pin "A1") (pinfunction "A1_A1") (pintype "bidirectional"))
    )
    (net (code "179") (name "unconnected-(J5-PadA7)") (class "Default")
      (node (ref "J5") (pin "A7") (pinfunction "A7_A7") (pintype "bidirectional"))
    )
    (net (code "180") (name "unconnected-(J5-PadB1)") (class "Default")
      (node (ref "J5") (pin "B1") (pinfunction "B1_B1") (pintype "bidirectional"))
    )
    (net (code "181") (name "unconnected-(J5-PadB6)") (class "Default")
      (node (ref "J5") (pin "B6") (pinfunction "B6_B6") (pintype "bidirectional"))
    )
    (net (code "182") (name "unconnected-(J5-PadB7)") (class "Default")
      (node (ref "J5") (pin "B7") (pinfunction "B7_B7") (pintype "bidirectional"))
    )
    (net (code "183") (name "unconnected-(J5-PadB8)") (class "Default")
      (node (ref "J5") (pin "B8") (pinfunction "B8_B8") (pintype "bidirectional"))
    )
    (net (code "184") (name "unconnected-(J5-PadC6)") (class "Default")
      (node (ref "J5") (pin "C6") (pinfunction "C6_C6") (pintype "bidirectional"))
    )
    (net (code "185") (name "unconnected-(J5-PadC8)") (class "Default")
      (node (ref "J5") (pin "C8") (pinfunction "C8_C8") (pintype "bidirectional"))
    )
    (net (code "186") (name "unconnected-(J5-PadD1)") (class "Default")
      (node (ref "J5") (pin "D1") (pinfunction "D1_D1") (pintype "bidirectional"))
    )
    (net (code "187") (name "unconnected-(J5-PadD7)") (class "Default")
      (node (ref "J5") (pin "D7") (pinfunction "D7_D7") (pintype "bidirectional"))
    )
    (net (code "188") (name "unconnected-(J5-PadE1)") (class "Default")
      (node (ref "J5") (pin "E1") (pinfunction "E1_E1") (pintype "bidirectional"))
    )
    (net (code "189") (name "unconnected-(J5-PadE6)") (class "Default")
      (node (ref "J5") (pin "E6") (pinfunction "E6_E6") (pintype "bidirectional"))
    )
    (net (code "190") (name "unconnected-(J5-PadE7)") (class "Default")
      (node (ref "J5") (pin "E7") (pinfunction "E7_E7") (pintype "bidirectional"))
    )
    (net (code "191") (name "unconnected-(J5-PadE8)") (class "Default")
      (node (ref "J5") (pin "E8") (pinfunction "E8_E8") (pintype "bidirectional"))
    )
    (net (code "192") (name "unconnected-(J5-PadF6)") (class "Default")
      (node (ref "J5") (pin "F6") (pinfunction "F6_F6") (pintype "bidirectional"))
    )
    (net (code "193") (name "unconnected-(J5-PadF8)") (class "Default")
      (node (ref "J5") (pin "F8") (pinfunction "F8_F8") (pintype "bidirectional"))
    )
    (net (code "194") (name "unconnected-(J5-PadG1)") (class "Default")
      (node (ref "J5") (pin "G1") (pinfunction "G1_G1") (pintype "bidirectional"))
    )
    (net (code "195") (name "unconnected-(J5-PadG7)") (class "Default")
      (node (ref "J5") (pin "G7") (pinfunction "G7_G7") (pintype "bidirectional"))
    )
    (net (code "196") (name "unconnected-(J5-PadH1)") (class "Default")
      (node (ref "J5") (pin "H1") (pinfunction "H1_H1") (pintype "bidirectional"))
    )
    (net (code "197") (name "unconnected-(J5-PadH6)") (class "Default")
      (node (ref "J5") (pin "H6") (pinfunction "H6_H6") (pintype "bidirectional"))
    )
    (net (code "198") (name "unconnected-(J5-PadH7)") (class "Default")
      (node (ref "J5") (pin "H7") (pinfunction "H7_H7") (pintype "bidirectional"))
    )
    (net (code "199") (name "unconnected-(J5-PadH8)") (class "Default")
      (node (ref "J5") (pin "H8") (pinfunction "H8_H8") (pintype "bidirectional"))
    )
    (net (code "200") (name "unconnected-(J5-PadI6)") (class "Default")
      (node (ref "J5") (pin "I6") (pinfunction "I6_I6") (pintype "bidirectional"))
    )
    (net (code "201") (name "unconnected-(J5-PadI8)") (class "Default")
      (node (ref "J5") (pin "I8") (pinfunction "I8_I8") (pintype "bidirectional"))
    )
    (net (code "202") (name "unconnected-(J5-PadJ1)") (class "Default")
      (node (ref "J5") (pin "J1") (pinfunction "J1_J1") (pintype "bidirectional"))
    )
    (net (code "203") (name "unconnected-(J5-PadJ7)") (class "Default")
      (node (ref "J5") (pin "J7") (pinfunction "J7_J7") (pintype "bidirectional"))
    )
    (net (code "204") (name "unconnected-(J5-PadK1)") (class "Default")
      (node (ref "J5") (pin "K1") (pinfunction "K1_K1") (pintype "bidirectional"))
    )
    (net (code "205") (name "unconnected-(J5-PadK6)") (class "Default")
      (node (ref "J5") (pin "K6") (pinfunction "K6_K6") (pintype "bidirectional"))
    )
    (net (code "206") (name "unconnected-(J5-PadK7)") (class "Default")
      (node (ref "J5") (pin "K7") (pinfunction "K7_K7") (pintype "bidirectional"))
    )
    (net (code "207") (name "unconnected-(J5-PadK8)") (class "Default")
      (node (ref "J5") (pin "K8") (pinfunction "K8_K8") (pintype "bidirectional"))
    )
    (net (code "208") (name "unconnected-(J5-PadL6)") (class "Default")
      (node (ref "J5") (pin "L6") (pinfunction "L6_L6") (pintype "bidirectional"))
    )
    (net (code "209") (name "unconnected-(J5-PadL8)") (class "Default")
      (node (ref "J5") (pin "L8") (pinfunction "L8_L8") (pintype "bidirectional"))
    )
  )
)
